# 990308_Schematic.net
KiCad netlist of a schematic drawn in Altium Designer
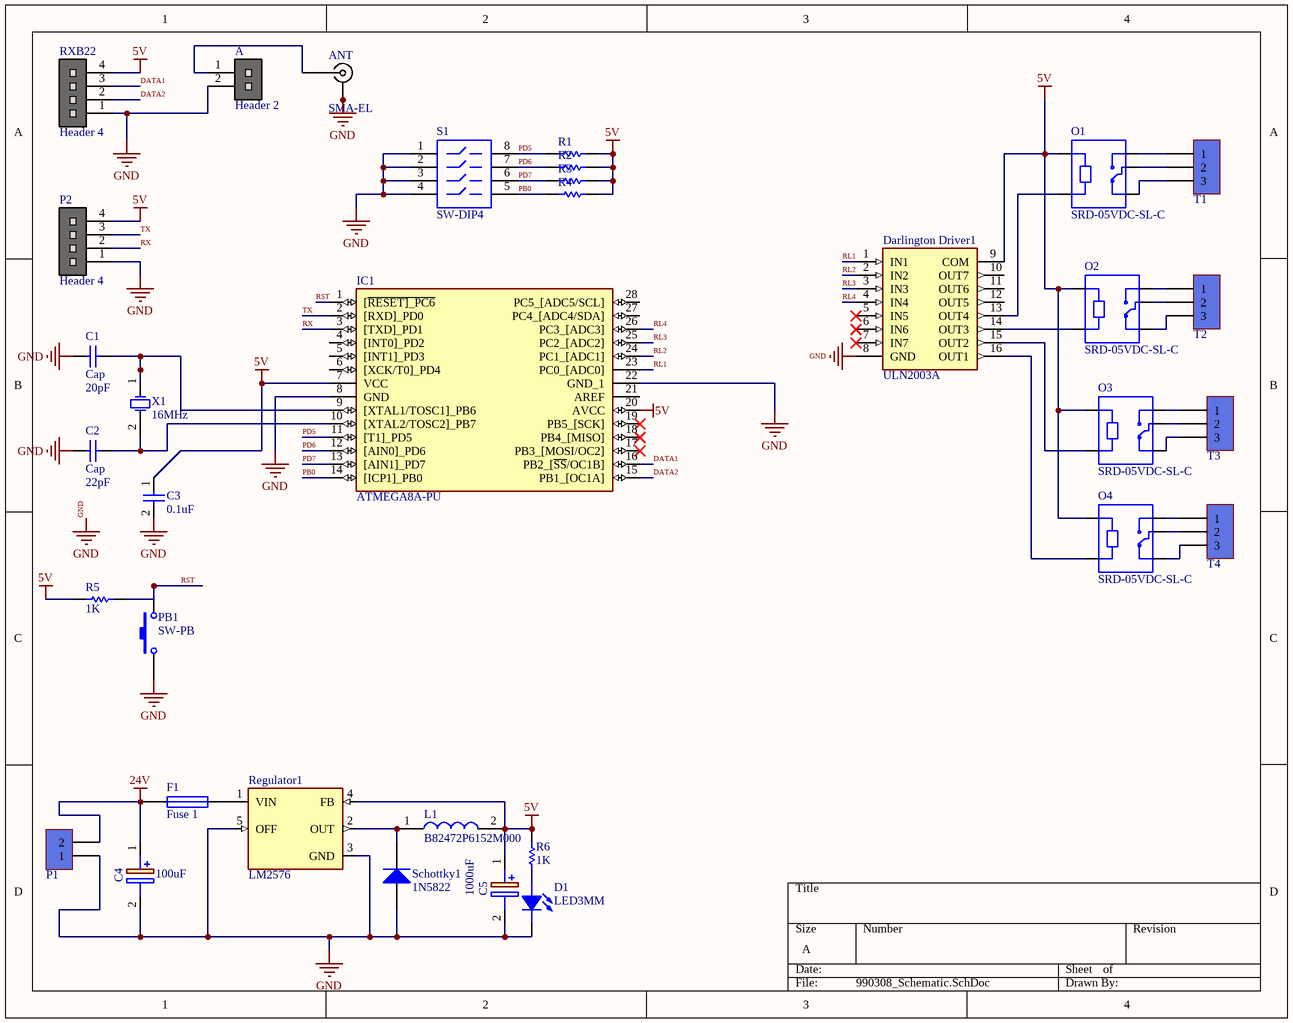
[diagram p0: 990308_Schematic.SchDoc]

(export (version "E")
  (design (tool "Eeschema 10.0.6"))
  (components
    (comp (ref "A")
      (value "Header 2")
      (footprint "HDR 1X2")
      (description "Header, 2-Pin")
      (libsource (lib "Ayric connectors") (part "Header 2"))
    )
    (comp (ref "ANT")
      (value "SMA-EL")
      (footprint "SMA-ENDLAUNCH")
      (description "SMA THREADED RF CONNECTOR VERTICAL")
      (libsource (lib "vh_altium_library") (part "SMA-EL"))
    )
    (comp (ref "C1")
      (value "Cap")
      (footprint "RAD-0.3")
      (description "Capacitor")
      (fields (field (name "ALTIUM_VALUE") "20pF") (field (name "PUBLISHER") "Altium Limited"))
      (libsource (lib "") (part "Cap_1"))
    )
    (comp (ref "C2")
      (value "Cap")
      (footprint "RAD-0.3")
      (description "Capacitor")
      (fields (field (name "ALTIUM_VALUE") "22pF") (field (name "PUBLISHER") "Altium Limited"))
      (libsource (lib "") (part "Cap_1"))
    )
    (comp (ref "C3")
      (value "0.1uF")
      (footprint "RAD-0.3")
      (description "Capacitor")
      (fields (field (name "PUBLISHER") "Altium Limited"))
      (libsource (lib "Miscellaneous Devices") (part "Cap"))
    )
    (comp (ref "C4")
      (value "100uF")
      (footprint "SamacSys:CAPPRD550W60D1050H2150")
      (description "Capacitor Polarised")
      (fields (field (name "MANUFACTURER_PART_NUMBER") "108CKE025M"))
      (libsource (lib "*") (part "108CKE025M"))
    )
    (comp (ref "C5")
      (value "1000uF")
      (footprint "SamacSys:CAPPRD550W60D1050H2150")
      (description "Capacitor Polarised")
      (fields (field (name "MANUFACTURER_PART_NUMBER") "108CKE025M"))
      (libsource (lib "*") (part "108CKE025M"))
    )
    (comp (ref "D1")
      (value "LED3MM")
      (footprint "LED3mm_GRN")
      (description "Light Emitting Diode")
      (fields (field (name "DESIGNER") "Ali Hafizi"))
      (libsource (lib "Altium") (part "LED 3MM"))
    )
    (comp (ref "Darlington Driver1")
      (value "ULN2003A")
      (footprint "SamacSys:DIP794W56P254L1918H533Q16N")
      (description "Integrated Circuit")
      (fields (field (name "MOUSER PART NUMBER") "511-ULN2003A") (field (name "RS PART NUMBER") "6868209"))
      (libsource (lib "*") (part "ULN2003A"))
    )
    (comp (ref "F1")
      (value "Fuse 1")
      (footprint "PIN-W2/E2.8")
      (description "Fuse")
      (fields (field (name "PUBLISHER") "Altium Limited"))
      (libsource (lib "Miscellaneous Devices") (part "Fuse 1"))
    )
    (comp (ref "IC1")
      (value "ATMEGA8A-PU")
      (footprint "SamacSys:DIP794W53P254L3467H457Q28N")
      (description "Integrated Circuit")
      (fields
        (field (name "MOUSER PART NUMBER") "556-ATMEGA8A-PU")
        (field (name "RS PART NUMBER") "1310372P")
      )
      (libsource (lib "*") (part "ATMEGA8A-PU"))
    )
    (comp (ref "L1")
      (value "B82472P6152M000")
      (footprint "SamacSys:INDPM7474X450N")
      (description "Inductor")
      (fields (field (name "MOUSER PART NUMBER") "871-B82472P6152M000"))
      (libsource (lib "*") (part "B82472P6152M000"))
    )
    (comp (ref "O1")
      (value "SRD-05VDC-SL-C")
      (footprint "RELAY_SRD-05VDC-SL-C")
      (fields (field (name "MF") "Songle Relay"))
      (libsource (lib "SRD-05VDC-SL-C") (part "SRD-05VDC-SL-C"))
    )
    (comp (ref "O2")
      (value "SRD-05VDC-SL-C")
      (footprint "RELAY_SRD-05VDC-SL-C")
      (fields (field (name "MF") "Songle Relay"))
      (libsource (lib "SRD-05VDC-SL-C") (part "SRD-05VDC-SL-C"))
    )
    (comp (ref "O3")
      (value "SRD-05VDC-SL-C")
      (footprint "RELAY_SRD-05VDC-SL-C")
      (fields (field (name "MF") "Songle Relay"))
      (libsource (lib "SRD-05VDC-SL-C") (part "SRD-05VDC-SL-C"))
    )
    (comp (ref "O4")
      (value "SRD-05VDC-SL-C")
      (footprint "RELAY_SRD-05VDC-SL-C")
      (fields (field (name "MF") "Songle Relay"))
      (libsource (lib "SRD-05VDC-SL-C") (part "SRD-05VDC-SL-C"))
    )
    (comp (ref "P1")
      (value "KF301_Terminal")
      (footprint "KF301 2PIN")
      (description "Terminal 2 Pin 250VAC 16A")
      (fields (field (name "DESIGNER") "Abbas Basereh"))
      (libsource (lib "Altium") (part "KF301-2Pin_Terminal"))
    )
    (comp (ref "P2")
      (value "Header 4")
      (footprint "HDR 1X4")
      (description "Header, 4-Pin")
      (libsource (lib "Ayric connectors") (part "Header 4"))
    )
    (comp (ref "PB1")
      (value "SW-PB")
      (footprint "SPST-2")
      (description "Switch")
      (fields (field (name "PUBLISHER") "Altium Limited"))
      (libsource (lib "Miscellaneous Devices") (part "SW-PB"))
    )
    (comp (ref "R1")
      (value "1K")
      (footprint "Axial 0_25w_2_54mm")
      (description "RES Axial 0.25W")
      (fields (field (name "DESIGNER") "Abbas Basereh"))
      (libsource (lib "Altium") (part "RES Axial 0.25W"))
    )
    (comp (ref "R2")
      (value "1K")
      (footprint "Axial 0_25w_2_54mm")
      (description "RES Axial 0.25W")
      (fields (field (name "DESIGNER") "Abbas Basereh"))
      (libsource (lib "Altium") (part "RES Axial 0.25W"))
    )
    (comp (ref "R3")
      (value "1K")
      (footprint "Axial 0_25w_2_54mm")
      (description "RES Axial 0.25W")
      (fields (field (name "DESIGNER") "Abbas Basereh"))
      (libsource (lib "Altium") (part "RES Axial 0.25W"))
    )
    (comp (ref "R4")
      (value "1K")
      (footprint "Axial 0_25w_2_54mm")
      (description "RES Axial 0.25W")
      (fields (field (name "DESIGNER") "Abbas Basereh"))
      (libsource (lib "Altium") (part "RES Axial 0.25W"))
    )
    (comp (ref "R5")
      (value "1K")
      (footprint "Axial 0_25w_2_54mm")
      (description "RES Axial 0.25W")
      (fields (field (name "DESIGNER") "Abbas Basereh"))
      (libsource (lib "Altium") (part "RES Axial 0.25W"))
    )
    (comp (ref "R6")
      (value "1K")
      (footprint "Axial 0_25w_2_54mm")
      (description "RES Axial 0.25W")
      (fields (field (name "DESIGNER") "Abbas Basereh"))
      (libsource (lib "Altium") (part "RES Axial 0.25W"))
    )
    (comp (ref "Regulator1")
      (value "LM2576")
      (footprint "TO220-5")
      (fields (field (name "MF") "Texas Instruments"))
      (libsource (lib "LM2576") (part "LM2576"))
    )
    (comp (ref "RXB22")
      (value "Header 4")
      (footprint "HDR 1X4")
      (description "Header, 4-Pin")
      (libsource (lib "Ayric connectors") (part "Header 4"))
    )
    (comp (ref "S1")
      (value "SW-DIP4")
      (footprint "DIP-8")
      (description "DIP Switch")
      (fields (field (name "PUBLISHER") "Altium Limited"))
      (libsource (lib "Miscellaneous Devices") (part "SW-DIP4"))
    )
    (comp (ref "Schottky1")
      (value "1N5822")
      (footprint "DO-41")
      (description "1 Amp General Purpose Rectifier")
      (fields (field (name "PUBLISHER") "Altium Limited"))
      (libsource (lib "Miscellaneous Devices") (part "Diode 1N4001"))
    )
    (comp (ref "T1")
      (value "KF301_Terminal")
      (footprint "KF301 3PIN")
      (description "Terminal 3 Pin 250VAC 16A")
      (fields (field (name "DESIGNER") "Abbas Basereh"))
      (libsource (lib "Altium") (part "KF301-3Pin_Terminal"))
    )
    (comp (ref "T2")
      (value "KF301_Terminal")
      (footprint "KF301 3PIN")
      (description "Terminal 3 Pin 250VAC 16A")
      (fields (field (name "DESIGNER") "Abbas Basereh"))
      (libsource (lib "Altium") (part "KF301-3Pin_Terminal"))
    )
    (comp (ref "T3")
      (value "KF301_Terminal")
      (footprint "KF301 3PIN")
      (description "Terminal 3 Pin 250VAC 16A")
      (fields (field (name "DESIGNER") "Abbas Basereh"))
      (libsource (lib "Altium") (part "KF301-3Pin_Terminal"))
    )
    (comp (ref "T4")
      (value "KF301_Terminal")
      (footprint "KF301 3PIN")
      (description "Terminal 3 Pin 250VAC 16A")
      (fields (field (name "DESIGNER") "Abbas Basereh"))
      (libsource (lib "Altium") (part "KF301-3Pin_Terminal"))
    )
    (comp (ref "X1")
      (value "16MHz")
      (footprint "XTAL Small")
      (description "XTAL Crystal")
      (libsource (lib "My Library") (part "XTAL"))
    )
  )
  (nets
    (net (code "1") (name "/DATA1") (class "Default")
      (node (ref "IC1") (pin "16") (pinfunction "PB2_[~{SS}/OC1B]_16") (pintype "bidirectional"))
      (node (ref "RXB22") (pin "3") (pinfunction "3_3") (pintype "passive"))
    )
    (net (code "2") (name "/DATA2") (class "Default")
      (node (ref "IC1") (pin "15") (pinfunction "PB1_[OC1A]_15") (pintype "bidirectional"))
      (node (ref "RXB22") (pin "2") (pinfunction "2_2") (pintype "passive"))
    )
    (net (code "3") (name "/PB0") (class "Default")
      (node (ref "IC1") (pin "14") (pinfunction "[ICP1]_PB0_14") (pintype "bidirectional"))
      (node (ref "R4") (pin "2") (pinfunction "2_2") (pintype "passive"))
      (node (ref "S1") (pin "5") (pinfunction "5_5") (pintype "passive"))
    )
    (net (code "4") (name "/PD5") (class "Default")
      (node (ref "IC1") (pin "11") (pinfunction "[T1]_PD5_11") (pintype "bidirectional"))
      (node (ref "R1") (pin "1") (pinfunction "1_1") (pintype "passive"))
      (node (ref "S1") (pin "8") (pinfunction "8_8") (pintype "passive"))
    )
    (net (code "5") (name "/PD6") (class "Default")
      (node (ref "IC1") (pin "12") (pinfunction "[AIN0]_PD6_12") (pintype "bidirectional"))
      (node (ref "R2") (pin "2") (pinfunction "2_2") (pintype "passive"))
      (node (ref "S1") (pin "7") (pinfunction "7_7") (pintype "passive"))
    )
    (net (code "6") (name "/PD7") (class "Default")
      (node (ref "IC1") (pin "13") (pinfunction "[AIN1]_PD7_13") (pintype "bidirectional"))
      (node (ref "R3") (pin "2") (pinfunction "2_2") (pintype "passive"))
      (node (ref "S1") (pin "6") (pinfunction "6_6") (pintype "passive"))
    )
    (net (code "7") (name "/RL1") (class "Default")
      (node (ref "Darlington Driver1") (pin "1") (pinfunction "IN1_1") (pintype "input"))
      (node (ref "IC1") (pin "23") (pinfunction "PC0_[ADC0]_23") (pintype "power_in"))
    )
    (net (code "8") (name "/RL2") (class "Default")
      (node (ref "Darlington Driver1") (pin "2") (pinfunction "IN2_2") (pintype "input"))
      (node (ref "IC1") (pin "24") (pinfunction "PC1_[ADC1]_24") (pintype "bidirectional"))
    )
    (net (code "9") (name "/RL3") (class "Default")
      (node (ref "Darlington Driver1") (pin "3") (pinfunction "IN3_3") (pintype "input"))
      (node (ref "IC1") (pin "25") (pinfunction "PC2_[ADC2]_25") (pintype "bidirectional"))
    )
    (net (code "10") (name "/RL4") (class "Default")
      (node (ref "Darlington Driver1") (pin "4") (pinfunction "IN4_4") (pintype "input"))
      (node (ref "IC1") (pin "26") (pinfunction "PC3_[ADC3]_26") (pintype "bidirectional"))
    )
    (net (code "11") (name "/RST") (class "Default")
      (node (ref "IC1") (pin "1") (pinfunction "[~{RESET]_PC6}_1") (pintype "bidirectional"))
      (node (ref "PB1") (pin "2") (pinfunction "2_2") (pintype "passive"))
      (node (ref "R5") (pin "1") (pinfunction "1_1") (pintype "passive"))
    )
    (net (code "12") (name "/RX") (class "Default")
      (node (ref "IC1") (pin "3") (pinfunction "[TXD]_PD1_3") (pintype "bidirectional"))
      (node (ref "P2") (pin "2") (pinfunction "2_2") (pintype "passive"))
    )
    (net (code "13") (name "/TX") (class "Default")
      (node (ref "IC1") (pin "2") (pinfunction "[RXD]_PD0_2") (pintype "bidirectional"))
      (node (ref "P2") (pin "3") (pinfunction "3_3") (pintype "passive"))
    )
    (net (code "14") (name "5V") (class "Default")
      (node (ref "C3") (pin "1") (pinfunction "1_1") (pintype "passive"))
      (node (ref "C5") (pin "1") (pinfunction "+_1") (pintype "passive"))
      (node (ref "Darlington Driver1") (pin "9") (pinfunction "COM_9") (pintype "passive"))
      (node (ref "IC1") (pin "20") (pinfunction "AVCC_20") (pintype "bidirectional"))
      (node (ref "IC1") (pin "7") (pinfunction "VCC_7") (pintype "power_in"))
      (node (ref "L1") (pin "2") (pinfunction "2_2") (pintype "passive"))
      (node (ref "O1") (pin "A1") (pinfunction "A1_A1") (pintype "passive"))
      (node (ref "O2") (pin "A1") (pinfunction "A1_A1") (pintype "passive"))
      (node (ref "O3") (pin "A1") (pinfunction "A1_A1") (pintype "passive"))
      (node (ref "O4") (pin "A1") (pinfunction "A1_A1") (pintype "passive"))
      (node (ref "P2") (pin "4") (pinfunction "4_4") (pintype "passive"))
      (node (ref "R1") (pin "2") (pinfunction "2_2") (pintype "passive"))
      (node (ref "R2") (pin "1") (pinfunction "1_1") (pintype "passive"))
      (node (ref "R3") (pin "1") (pinfunction "1_1") (pintype "passive"))
      (node (ref "R4") (pin "1") (pinfunction "1_1") (pintype "passive"))
      (node (ref "R5") (pin "2") (pinfunction "2_2") (pintype "passive"))
      (node (ref "R6") (pin "1") (pinfunction "1_1") (pintype "passive"))
      (node (ref "RXB22") (pin "4") (pinfunction "4_4") (pintype "passive"))
      (node (ref "Regulator1") (pin "4") (pinfunction "FB_4") (pintype "input"))
    )
    (net (code "15") (name "24V") (class "Default")
      (node (ref "C4") (pin "1") (pinfunction "+_1") (pintype "passive"))
      (node (ref "F1") (pin "1") (pinfunction "1_1") (pintype "passive"))
      (node (ref "P1") (pin "2") (pinfunction "2_2") (pintype "passive"))
    )
    (net (code "16") (name "GND") (class "Default")
      (node (ref "A") (pin "2") (pinfunction "2_2") (pintype "passive"))
      (node (ref "ANT") (pin "2") (pinfunction "2_2") (pintype "passive"))
      (node (ref "ANT") (pin "3") (pinfunction "3_3") (pintype "passive"))
      (node (ref "ANT") (pin "4") (pinfunction "4_4") (pintype "passive"))
      (node (ref "ANT") (pin "5") (pinfunction "5_5") (pintype "passive"))
      (node (ref "C1") (pin "1") (pinfunction "1_1") (pintype "passive"))
      (node (ref "C2") (pin "1") (pinfunction "1_1") (pintype "passive"))
      (node (ref "C3") (pin "2") (pinfunction "2_2") (pintype "passive"))
      (node (ref "C4") (pin "2") (pinfunction "-_2") (pintype "passive"))
      (node (ref "C5") (pin "2") (pinfunction "-_2") (pintype "passive"))
      (node (ref "D1") (pin "2") (pinfunction "CATHODE_2") (pintype "passive"))
      (node (ref "Darlington Driver1") (pin "8") (pinfunction "GND_8") (pintype "power_in"))
      (node (ref "IC1") (pin "22") (pinfunction "GND_1_22") (pintype "power_in"))
      (node (ref "IC1") (pin "8") (pinfunction "GND_8") (pintype "power_in"))
      (node (ref "P1") (pin "1") (pinfunction "1_1") (pintype "passive"))
      (node (ref "P2") (pin "1") (pinfunction "1_1") (pintype "passive"))
      (node (ref "PB1") (pin "1") (pinfunction "1_1") (pintype "passive"))
      (node (ref "RXB22") (pin "1") (pinfunction "1_1") (pintype "passive"))
      (node (ref "Regulator1") (pin "3") (pinfunction "GND_3") (pintype "power_in"))
      (node (ref "Regulator1") (pin "5") (pinfunction "OFF_5") (pintype "input"))
      (node (ref "S1") (pin "1") (pinfunction "1_1") (pintype "passive"))
      (node (ref "S1") (pin "2") (pinfunction "2_2") (pintype "passive"))
      (node (ref "S1") (pin "3") (pinfunction "3_3") (pintype "passive"))
      (node (ref "S1") (pin "4") (pinfunction "4_4") (pintype "passive"))
      (node (ref "Schottky1") (pin "1") (pinfunction "A_1") (pintype "passive"))
    )
    (net (code "17") (name "Net-(A-Pad1)") (class "Default")
      (node (ref "A") (pin "1") (pinfunction "1_1") (pintype "passive"))
      (node (ref "ANT") (pin "1") (pinfunction "1_1") (pintype "passive"))
    )
    (net (code "18") (name "Net-(D1-ANODE)") (class "Default")
      (node (ref "D1") (pin "1") (pinfunction "ANODE_1") (pintype "passive"))
      (node (ref "R6") (pin "2") (pinfunction "2_2") (pintype "passive"))
    )
    (net (code "19") (name "Net-(Darlington Driver1-OUT1)") (class "Default")
      (node (ref "Darlington Driver1") (pin "16") (pinfunction "OUT1_16") (pintype "output"))
      (node (ref "O4") (pin "A2") (pinfunction "A2_A2") (pintype "passive"))
    )
    (net (code "20") (name "Net-(Darlington Driver1-OUT2)") (class "Default")
      (node (ref "Darlington Driver1") (pin "15") (pinfunction "OUT2_15") (pintype "output"))
      (node (ref "O3") (pin "A2") (pinfunction "A2_A2") (pintype "passive"))
    )
    (net (code "21") (name "Net-(Darlington Driver1-OUT3)") (class "Default")
      (node (ref "Darlington Driver1") (pin "14") (pinfunction "OUT3_14") (pintype "output"))
      (node (ref "O2") (pin "A2") (pinfunction "A2_A2") (pintype "passive"))
    )
    (net (code "22") (name "Net-(Darlington Driver1-OUT4)") (class "Default")
      (node (ref "Darlington Driver1") (pin "13") (pinfunction "OUT4_13") (pintype "output"))
      (node (ref "O1") (pin "A2") (pinfunction "A2_A2") (pintype "passive"))
    )
    (net (code "23") (name "Net-(IC1-[XTAL1{slash}TOSC1]_PB6)") (class "Default")
      (node (ref "C1") (pin "2") (pinfunction "2_2") (pintype "passive"))
      (node (ref "IC1") (pin "9") (pinfunction "[XTAL1/TOSC1]_PB6_9") (pintype "bidirectional"))
      (node (ref "X1") (pin "1") (pinfunction "OSC1_1") (pintype "passive"))
    )
    (net (code "24") (name "Net-(IC1-[XTAL2{slash}TOSC2]_PB7)") (class "Default")
      (node (ref "C2") (pin "2") (pinfunction "2_2") (pintype "passive"))
      (node (ref "IC1") (pin "10") (pinfunction "[XTAL2/TOSC2]_PB7_10") (pintype "bidirectional"))
      (node (ref "X1") (pin "2") (pinfunction "OSC2_2") (pintype "passive"))
    )
    (net (code "25") (name "Net-(O1-PadCOM)") (class "Default")
      (node (ref "O1") (pin "COM") (pinfunction "COM_COM") (pintype "passive"))
      (node (ref "T1") (pin "2") (pinfunction "2_2") (pintype "passive"))
    )
    (net (code "26") (name "Net-(O1-PadNC)") (class "Default")
      (node (ref "O1") (pin "NC") (pinfunction "NC_NC") (pintype "passive"))
      (node (ref "T1") (pin "3") (pinfunction "3_3") (pintype "passive"))
    )
    (net (code "27") (name "Net-(O1-PadNO)") (class "Default")
      (node (ref "O1") (pin "NO") (pinfunction "NO_NO") (pintype "passive"))
      (node (ref "T1") (pin "1") (pinfunction "1_1") (pintype "passive"))
    )
    (net (code "28") (name "Net-(O2-PadCOM)") (class "Default")
      (node (ref "O2") (pin "COM") (pinfunction "COM_COM") (pintype "passive"))
      (node (ref "T2") (pin "2") (pinfunction "2_2") (pintype "passive"))
    )
    (net (code "29") (name "Net-(O2-PadNC)") (class "Default")
      (node (ref "O2") (pin "NC") (pinfunction "NC_NC") (pintype "passive"))
      (node (ref "T2") (pin "3") (pinfunction "3_3") (pintype "passive"))
    )
    (net (code "30") (name "Net-(O2-PadNO)") (class "Default")
      (node (ref "O2") (pin "NO") (pinfunction "NO_NO") (pintype "passive"))
      (node (ref "T2") (pin "1") (pinfunction "1_1") (pintype "passive"))
    )
    (net (code "31") (name "Net-(O3-PadCOM)") (class "Default")
      (node (ref "O3") (pin "COM") (pinfunction "COM_COM") (pintype "passive"))
      (node (ref "T3") (pin "2") (pinfunction "2_2") (pintype "passive"))
    )
    (net (code "32") (name "Net-(O3-PadNC)") (class "Default")
      (node (ref "O3") (pin "NC") (pinfunction "NC_NC") (pintype "passive"))
      (node (ref "T3") (pin "3") (pinfunction "3_3") (pintype "passive"))
    )
    (net (code "33") (name "Net-(O3-PadNO)") (class "Default")
      (node (ref "O3") (pin "NO") (pinfunction "NO_NO") (pintype "passive"))
      (node (ref "T3") (pin "1") (pinfunction "1_1") (pintype "passive"))
    )
    (net (code "34") (name "Net-(O4-PadCOM)") (class "Default")
      (node (ref "O4") (pin "COM") (pinfunction "COM_COM") (pintype "passive"))
      (node (ref "T4") (pin "2") (pinfunction "2_2") (pintype "passive"))
    )
    (net (code "35") (name "Net-(O4-PadNC)") (class "Default")
      (node (ref "O4") (pin "NC") (pinfunction "NC_NC") (pintype "passive"))
      (node (ref "T4") (pin "3") (pinfunction "3_3") (pintype "passive"))
    )
    (net (code "36") (name "Net-(O4-PadNO)") (class "Default")
      (node (ref "O4") (pin "NO") (pinfunction "NO_NO") (pintype "passive"))
      (node (ref "T4") (pin "1") (pinfunction "1_1") (pintype "passive"))
    )
    (net (code "37") (name "Net-(Regulator1-OUT)") (class "Default")
      (node (ref "L1") (pin "1") (pinfunction "1_1") (pintype "passive"))
      (node (ref "Regulator1") (pin "2") (pinfunction "OUT_2") (pintype "output"))
      (node (ref "Schottky1") (pin "2") (pinfunction "K_2") (pintype "passive"))
    )
    (net (code "38") (name "Net-(Regulator1-VIN)") (class "Default")
      (node (ref "F1") (pin "2") (pinfunction "2_2") (pintype "passive"))
      (node (ref "Regulator1") (pin "1") (pinfunction "VIN_1") (pintype "power_in"))
    )
    (net (code "39") (name "unconnected-(Darlington Driver1-IN5-Pad5)") (class "Default")
      (node (ref "Darlington Driver1") (pin "5") (pinfunction "IN5_5") (pintype "input+no_connect"))
    )
    (net (code "40") (name "unconnected-(Darlington Driver1-IN6-Pad6)") (class "Default")
      (node (ref "Darlington Driver1") (pin "6") (pinfunction "IN6_6") (pintype "input+no_connect"))
    )
    (net (code "41") (name "unconnected-(Darlington Driver1-IN7-Pad7)") (class "Default")
      (node (ref "Darlington Driver1") (pin "7") (pinfunction "IN7_7") (pintype "input+no_connect"))
    )
    (net (code "42") (name "unconnected-(Darlington Driver1-OUT5-Pad12)") (class "Default")
      (node (ref "Darlington Driver1") (pin "12") (pinfunction "OUT5_12") (pintype "output"))
    )
    (net (code "43") (name "unconnected-(Darlington Driver1-OUT6-Pad11)") (class "Default")
      (node (ref "Darlington Driver1") (pin "11") (pinfunction "OUT6_11") (pintype "output"))
    )
    (net (code "44") (name "unconnected-(Darlington Driver1-OUT7-Pad10)") (class "Default")
      (node (ref "Darlington Driver1") (pin "10") (pinfunction "OUT7_10") (pintype "output"))
    )
    (net (code "45") (name "unconnected-(IC1-AREF-Pad21)") (class "Default")
      (node (ref "IC1") (pin "21") (pinfunction "AREF_21") (pintype "power_in"))
    )
    (net (code "46") (name "unconnected-(IC1-PB3_[MOSI{slash}OC2]-Pad17)") (class "Default")
      (node (ref "IC1") (pin "17") (pinfunction "PB3_[MOSI/OC2]_17") (pintype "bidirectional+no_connect"))
    )
    (net (code "47") (name "unconnected-(IC1-PB4_[MISO]-Pad18)") (class "Default")
      (node (ref "IC1") (pin "18") (pinfunction "PB4_[MISO]_18") (pintype "bidirectional+no_connect"))
    )
    (net (code "48") (name "unconnected-(IC1-PB5_[SCK]-Pad19)") (class "Default")
      (node (ref "IC1") (pin "19") (pinfunction "PB5_[SCK]_19") (pintype "bidirectional+no_connect"))
    )
    (net (code "49") (name "unconnected-(IC1-PC4_[ADC4{slash}SDA]-Pad27)") (class "Default")
      (node (ref "IC1") (pin "27") (pinfunction "PC4_[ADC4/SDA]_27") (pintype "bidirectional"))
    )
    (net (code "50") (name "unconnected-(IC1-PC5_[ADC5{slash}SCL]-Pad28)") (class "Default")
      (node (ref "IC1") (pin "28") (pinfunction "PC5_[ADC5/SCL]_28") (pintype "bidirectional"))
    )
    (net (code "51") (name "unconnected-(IC1-[INT0]_PD2-Pad4)") (class "Default")
      (node (ref "IC1") (pin "4") (pinfunction "[INT0]_PD2_4") (pintype "bidirectional"))
    )
    (net (code "52") (name "unconnected-(IC1-[INT1]_PD3-Pad5)") (class "Default")
      (node (ref "IC1") (pin "5") (pinfunction "[INT1]_PD3_5") (pintype "bidirectional"))
    )
    (net (code "53") (name "unconnected-(IC1-[XCK{slash}T0]_PD4-Pad6)") (class "Default")
      (node (ref "IC1") (pin "6") (pinfunction "[XCK/T0]_PD4_6") (pintype "bidirectional"))
    )
  )
)
